# InterfacesA_USBFTDI.net
KiCad netlist of a schematic drawn in Altium Designer
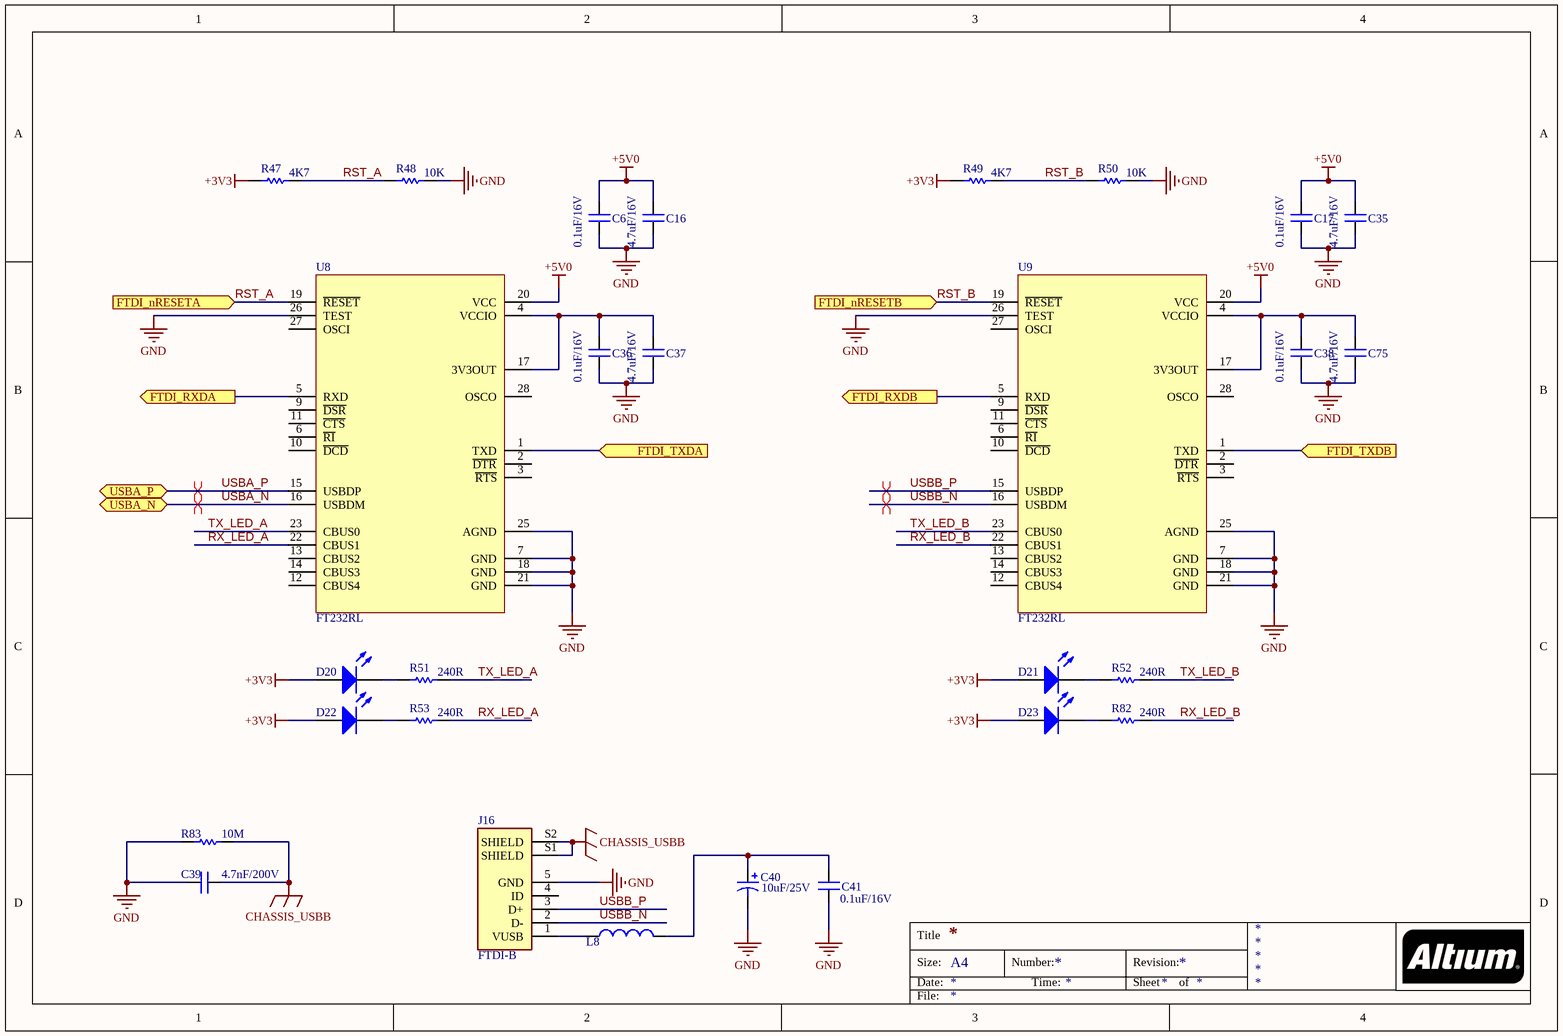
[diagram p0: InterfacesA_USBFTDI.SchDoc]

(export (version "E")
  (design (tool "Eeschema 10.0.6"))
  (components
    (comp (ref "C6")
      (value "0.1uF/16V")
      (footprint "CAP_0805")
      (fields (field (name "Comment") "CAP_0805"))
      (libsource (lib "LibSGQB") (part "CAP_0603"))
    )
    (comp (ref "C16")
      (value "4.7uF/16V")
      (footprint "CAP_0805")
      (fields (field (name "Comment") "CAP_0805"))
      (libsource (lib "LibSGQB") (part "CAP_0603"))
    )
    (comp (ref "C17")
      (value "0.1uF/16V")
      (footprint "CAP_0805")
      (fields (field (name "Comment") "CAP_0805"))
      (libsource (lib "LibSGQB") (part "CAP_0603"))
    )
    (comp (ref "C35")
      (value "4.7uF/16V")
      (footprint "CAP_0805")
      (fields (field (name "Comment") "CAP_0805"))
      (libsource (lib "LibSGQB") (part "CAP_0603"))
    )
    (comp (ref "C36")
      (value "0.1uF/16V")
      (footprint "CAP_0805")
      (fields (field (name "Comment") "CAP_0805"))
      (libsource (lib "LibSGQB") (part "CAP_0603"))
    )
    (comp (ref "C37")
      (value "4.7uF/16V")
      (footprint "CAP_0805")
      (fields (field (name "Comment") "CAP_0805"))
      (libsource (lib "LibSGQB") (part "CAP_0603"))
    )
    (comp (ref "C38")
      (value "0.1uF/16V")
      (footprint "CAP_0805")
      (fields (field (name "Comment") "CAP_0805"))
      (libsource (lib "LibSGQB") (part "CAP_0603"))
    )
    (comp (ref "C39")
      (value "4.7nF/200V")
      (footprint "CAP_0805")
      (fields (field (name "Comment") "CAP_0805"))
      (libsource (lib "AdapterLib") (part "CAP_0805"))
    )
    (comp (ref "C40")
      (value "10uF/25V")
      (footprint "CASE-C")
      (fields (field (name "Comment") "CASE-C"))
      (libsource (lib "AdapterLib") (part "CASE-C"))
    )
    (comp (ref "C41")
      (value "0.1uF/16V")
      (footprint "CAP_0805")
      (fields (field (name "Comment") "CAP_0805"))
      (libsource (lib "AdapterLib") (part "CAP_0805"))
    )
    (comp (ref "C75")
      (value "4.7uF/16V")
      (footprint "CAP_0805")
      (fields (field (name "Comment") "CAP_0805"))
      (libsource (lib "LibSGQB") (part "CAP_0603"))
    )
    (comp (ref "D20")
      (value "LED_0603")
      (footprint "LED_0603")
      (libsource (lib "AdapterLib") (part "LED_0603"))
    )
    (comp (ref "D21")
      (value "LED_0603")
      (footprint "LED_0603")
      (libsource (lib "AdapterLib") (part "LED_0603"))
    )
    (comp (ref "D22")
      (value "LED_0603")
      (footprint "LED_0603")
      (libsource (lib "AdapterLib") (part "LED_0603"))
    )
    (comp (ref "D23")
      (value "LED_0603")
      (footprint "LED_0603")
      (libsource (lib "AdapterLib") (part "LED_0603"))
    )
    (comp (ref "J16")
      (value "FTDI-B")
      (footprint "UX60-MB-5S8")
      (description "USB MINI TYPE B")
      (libsource (lib "AdapterLib") (part "UX60-MB-5S8"))
    )
    (comp (ref "L8")
      (value "IND_0805")
      (footprint "IND_0805")
      (libsource (lib "AdapterLib") (part "IND_0805"))
    )
    (comp (ref "R47")
      (value "4K7")
      (footprint "RES_0805")
      (fields (field (name "Comment") "RES_0805"))
      (libsource (lib "AdapterLib") (part "RES_0805"))
    )
    (comp (ref "R48")
      (value "10K")
      (footprint "RES_0805")
      (fields (field (name "Comment") "RES_0805"))
      (libsource (lib "AdapterLib") (part "RES_0805"))
    )
    (comp (ref "R49")
      (value "4K7")
      (footprint "RES_0805")
      (fields (field (name "Comment") "RES_0805"))
      (libsource (lib "AdapterLib") (part "RES_0805"))
    )
    (comp (ref "R50")
      (value "10K")
      (footprint "RES_0805")
      (fields (field (name "Comment") "RES_0805"))
      (libsource (lib "AdapterLib") (part "RES_0805"))
    )
    (comp (ref "R51")
      (value "240R")
      (footprint "RES_0805")
      (fields (field (name "Comment") "RES_0805"))
      (libsource (lib "AdapterLib") (part "RES_0805"))
    )
    (comp (ref "R52")
      (value "240R")
      (footprint "RES_0805")
      (fields (field (name "Comment") "RES_0805"))
      (libsource (lib "AdapterLib") (part "RES_0805"))
    )
    (comp (ref "R53")
      (value "240R")
      (footprint "RES_0805")
      (fields (field (name "Comment") "RES_0805"))
      (libsource (lib "AdapterLib") (part "RES_0805"))
    )
    (comp (ref "R82")
      (value "240R")
      (footprint "RES_0805")
      (fields (field (name "Comment") "RES_0805"))
      (libsource (lib "AdapterLib") (part "RES_0805"))
    )
    (comp (ref "R83")
      (value "10M")
      (footprint "RES_0805")
      (fields (field (name "Comment") "RES_0805"))
      (libsource (lib "AdapterLib") (part "RES_0805"))
    )
    (comp (ref "U8")
      (value "FT232RL")
      (footprint "AdapterLib:FT232RL")
      (description "USB Bridge, USB to UART USB 2.0 UART Interface 28-SSOP")
      (fields (field (name "DIGI-KEY_PART_NUMBER") "768-1007-1-ND") (field (name "MP") "FT232RL-REEL"))
      (libsource (lib "AdapterLib") (part "FT232RL"))
    )
    (comp (ref "U9")
      (value "FT232RL")
      (footprint "AdapterLib:FT232RL")
      (description "USB Bridge, USB to UART USB 2.0 UART Interface 28-SSOP")
      (fields (field (name "DIGI-KEY_PART_NUMBER") "768-1007-1-ND") (field (name "MP") "FT232RL-REEL"))
      (libsource (lib "AdapterLib") (part "FT232RL"))
    )
  )
  (nets
    (net (code "1") (name "+3V3") (class "Default")
      (node (ref "D20") (pin "1") (pinfunction "A_1") (pintype "passive"))
      (node (ref "D21") (pin "1") (pinfunction "A_1") (pintype "passive"))
      (node (ref "D22") (pin "1") (pinfunction "A_1") (pintype "passive"))
      (node (ref "D23") (pin "1") (pinfunction "A_1") (pintype "passive"))
      (node (ref "R47") (pin "1") (pinfunction "1_1") (pintype "passive"))
      (node (ref "R49") (pin "1") (pinfunction "1_1") (pintype "passive"))
    )
    (net (code "2") (name "+5V0") (class "Default")
      (node (ref "C16") (pin "1") (pinfunction "1_1") (pintype "passive"))
      (node (ref "C17") (pin "1") (pinfunction "1_1") (pintype "passive"))
      (node (ref "C35") (pin "1") (pinfunction "1_1") (pintype "passive"))
      (node (ref "C6") (pin "1") (pinfunction "1_1") (pintype "passive"))
      (node (ref "U8") (pin "20") (pinfunction "VCC_20") (pintype "passive"))
      (node (ref "U9") (pin "20") (pinfunction "VCC_20") (pintype "passive"))
    )
    (net (code "3") (name "/FTDI_RXDA") (class "Default")
      (node (ref "U8") (pin "5") (pinfunction "RXD_5") (pintype "passive"))
    )
    (net (code "4") (name "/FTDI_RXDB") (class "Default")
      (node (ref "U9") (pin "5") (pinfunction "RXD_5") (pintype "passive"))
    )
    (net (code "5") (name "/FTDI_TXDA") (class "Default")
      (node (ref "U8") (pin "1") (pinfunction "TXD_1") (pintype "passive"))
    )
    (net (code "6") (name "/FTDI_TXDB") (class "Default")
      (node (ref "U9") (pin "1") (pinfunction "TXD_1") (pintype "passive"))
    )
    (net (code "7") (name "/RST_A") (class "Default")
      (node (ref "R47") (pin "2") (pinfunction "2_2") (pintype "passive"))
      (node (ref "R48") (pin "1") (pinfunction "1_1") (pintype "passive"))
      (node (ref "U8") (pin "19") (pinfunction "~{RESET}_19") (pintype "passive"))
    )
    (net (code "8") (name "/RST_B") (class "Default")
      (node (ref "R49") (pin "2") (pinfunction "2_2") (pintype "passive"))
      (node (ref "R50") (pin "1") (pinfunction "1_1") (pintype "passive"))
      (node (ref "U9") (pin "19") (pinfunction "~{RESET}_19") (pintype "passive"))
    )
    (net (code "9") (name "/RX_LED_A") (class "Default")
      (node (ref "R53") (pin "2") (pinfunction "2_2") (pintype "passive"))
      (node (ref "U8") (pin "22") (pinfunction "CBUS1_22") (pintype "passive"))
    )
    (net (code "10") (name "/RX_LED_B") (class "Default")
      (node (ref "R82") (pin "2") (pinfunction "2_2") (pintype "passive"))
      (node (ref "U9") (pin "22") (pinfunction "CBUS1_22") (pintype "passive"))
    )
    (net (code "11") (name "/TX_LED_A") (class "Default")
      (node (ref "R51") (pin "2") (pinfunction "2_2") (pintype "passive"))
      (node (ref "U8") (pin "23") (pinfunction "CBUS0_23") (pintype "passive"))
    )
    (net (code "12") (name "/TX_LED_B") (class "Default")
      (node (ref "R52") (pin "2") (pinfunction "2_2") (pintype "passive"))
      (node (ref "U9") (pin "23") (pinfunction "CBUS0_23") (pintype "passive"))
    )
    (net (code "13") (name "/USBA_N") (class "Default")
      (node (ref "U8") (pin "16") (pinfunction "USBDM_16") (pintype "passive"))
    )
    (net (code "14") (name "/USBA_P") (class "Default")
      (node (ref "U8") (pin "15") (pinfunction "USBDP_15") (pintype "passive"))
    )
    (net (code "15") (name "/USBB_N") (class "Default")
      (node (ref "J16") (pin "2") (pinfunction "D-_2") (pintype "passive"))
      (node (ref "U9") (pin "16") (pinfunction "USBDM_16") (pintype "passive"))
    )
    (net (code "16") (name "/USBB_P") (class "Default")
      (node (ref "J16") (pin "3") (pinfunction "D+_3") (pintype "passive"))
      (node (ref "U9") (pin "15") (pinfunction "USBDP_15") (pintype "passive"))
    )
    (net (code "17") (name "CHASSIS_USBB") (class "Default")
      (node (ref "C39") (pin "1") (pinfunction "1_1") (pintype "passive"))
      (node (ref "J16") (pin "S1") (pinfunction "SHIELD_S1") (pintype "passive"))
      (node (ref "J16") (pin "S2") (pinfunction "SHIELD_S2") (pintype "passive"))
      (node (ref "R83") (pin "1") (pinfunction "1_1") (pintype "passive"))
    )
    (net (code "18") (name "GND") (class "Default")
      (node (ref "C16") (pin "2") (pinfunction "2_2") (pintype "passive"))
      (node (ref "C17") (pin "2") (pinfunction "2_2") (pintype "passive"))
      (node (ref "C35") (pin "2") (pinfunction "2_2") (pintype "passive"))
      (node (ref "C36") (pin "2") (pinfunction "2_2") (pintype "passive"))
      (node (ref "C37") (pin "2") (pinfunction "2_2") (pintype "passive"))
      (node (ref "C38") (pin "2") (pinfunction "2_2") (pintype "passive"))
      (node (ref "C39") (pin "2") (pinfunction "2_2") (pintype "passive"))
      (node (ref "C40") (pin "K") (pinfunction "2_K") (pintype "passive"))
      (node (ref "C41") (pin "1") (pinfunction "1_1") (pintype "passive"))
      (node (ref "C6") (pin "2") (pinfunction "2_2") (pintype "passive"))
      (node (ref "C75") (pin "2") (pinfunction "2_2") (pintype "passive"))
      (node (ref "J16") (pin "5") (pinfunction "GND_5") (pintype "passive"))
      (node (ref "R48") (pin "2") (pinfunction "2_2") (pintype "passive"))
      (node (ref "R50") (pin "2") (pinfunction "2_2") (pintype "passive"))
      (node (ref "R83") (pin "2") (pinfunction "2_2") (pintype "passive"))
      (node (ref "U8") (pin "18") (pinfunction "GND_18") (pintype "passive"))
      (node (ref "U8") (pin "21") (pinfunction "GND_21") (pintype "passive"))
      (node (ref "U8") (pin "25") (pinfunction "AGND_25") (pintype "passive"))
      (node (ref "U8") (pin "26") (pinfunction "TEST_26") (pintype "passive"))
      (node (ref "U8") (pin "7") (pinfunction "GND_7") (pintype "passive"))
      (node (ref "U9") (pin "18") (pinfunction "GND_18") (pintype "passive"))
      (node (ref "U9") (pin "21") (pinfunction "GND_21") (pintype "passive"))
      (node (ref "U9") (pin "25") (pinfunction "AGND_25") (pintype "passive"))
      (node (ref "U9") (pin "26") (pinfunction "TEST_26") (pintype "passive"))
      (node (ref "U9") (pin "7") (pinfunction "GND_7") (pintype "passive"))
    )
    (net (code "19") (name "Net-(C40-1)") (class "Default")
      (node (ref "C40") (pin "A") (pinfunction "1_A") (pintype "passive"))
      (node (ref "C41") (pin "2") (pinfunction "2_2") (pintype "passive"))
      (node (ref "L8") (pin "2") (pinfunction "2_2") (pintype "passive"))
    )
    (net (code "20") (name "Net-(D20-K)") (class "Default")
      (node (ref "D20") (pin "2") (pinfunction "K_2") (pintype "passive"))
      (node (ref "R51") (pin "1") (pinfunction "1_1") (pintype "passive"))
    )
    (net (code "21") (name "Net-(D21-K)") (class "Default")
      (node (ref "D21") (pin "2") (pinfunction "K_2") (pintype "passive"))
      (node (ref "R52") (pin "1") (pinfunction "1_1") (pintype "passive"))
    )
    (net (code "22") (name "Net-(D22-K)") (class "Default")
      (node (ref "D22") (pin "2") (pinfunction "K_2") (pintype "passive"))
      (node (ref "R53") (pin "1") (pinfunction "1_1") (pintype "passive"))
    )
    (net (code "23") (name "Net-(D23-K)") (class "Default")
      (node (ref "D23") (pin "2") (pinfunction "K_2") (pintype "passive"))
      (node (ref "R82") (pin "1") (pinfunction "1_1") (pintype "passive"))
    )
    (net (code "24") (name "Net-(J16-VUSB)") (class "Default")
      (node (ref "J16") (pin "1") (pinfunction "VUSB_1") (pintype "passive"))
      (node (ref "L8") (pin "1") (pinfunction "1_1") (pintype "passive"))
    )
    (net (code "25") (name "Net-(U8-3V3OUT)") (class "Default")
      (node (ref "C36") (pin "1") (pinfunction "1_1") (pintype "passive"))
      (node (ref "C37") (pin "1") (pinfunction "1_1") (pintype "passive"))
      (node (ref "U8") (pin "17") (pinfunction "3V3OUT_17") (pintype "passive"))
      (node (ref "U8") (pin "4") (pinfunction "VCCIO_4") (pintype "passive"))
    )
    (net (code "26") (name "Net-(U9-3V3OUT)") (class "Default")
      (node (ref "C38") (pin "1") (pinfunction "1_1") (pintype "passive"))
      (node (ref "C75") (pin "1") (pinfunction "1_1") (pintype "passive"))
      (node (ref "U9") (pin "17") (pinfunction "3V3OUT_17") (pintype "passive"))
      (node (ref "U9") (pin "4") (pinfunction "VCCIO_4") (pintype "passive"))
    )
    (net (code "27") (name "unconnected-(J16-ID-Pad4)") (class "Default")
      (node (ref "J16") (pin "4") (pinfunction "ID_4") (pintype "passive"))
    )
    (net (code "28") (name "unconnected-(U8-CBUS2-Pad13)") (class "Default")
      (node (ref "U8") (pin "13") (pinfunction "CBUS2_13") (pintype "passive"))
    )
    (net (code "29") (name "unconnected-(U8-CBUS3-Pad14)") (class "Default")
      (node (ref "U8") (pin "14") (pinfunction "CBUS3_14") (pintype "passive"))
    )
    (net (code "30") (name "unconnected-(U8-CBUS4-Pad12)") (class "Default")
      (node (ref "U8") (pin "12") (pinfunction "CBUS4_12") (pintype "passive"))
    )
    (net (code "31") (name "unconnected-(U8-OSCI-Pad27)") (class "Default")
      (node (ref "U8") (pin "27") (pinfunction "OSCI_27") (pintype "passive"))
    )
    (net (code "32") (name "unconnected-(U8-OSCO-Pad28)") (class "Default")
      (node (ref "U8") (pin "28") (pinfunction "OSCO_28") (pintype "passive"))
    )
    (net (code "33") (name "unconnected-(U8-~{CTS}-Pad11)") (class "Default")
      (node (ref "U8") (pin "11") (pinfunction "~{CTS}_11") (pintype "passive"))
    )
    (net (code "34") (name "unconnected-(U8-~{DCD}-Pad10)") (class "Default")
      (node (ref "U8") (pin "10") (pinfunction "~{DCD}_10") (pintype "passive"))
    )
    (net (code "35") (name "unconnected-(U8-~{DSR}-Pad9)") (class "Default")
      (node (ref "U8") (pin "9") (pinfunction "~{DSR}_9") (pintype "passive"))
    )
    (net (code "36") (name "unconnected-(U8-~{DTR}-Pad2)") (class "Default")
      (node (ref "U8") (pin "2") (pinfunction "~{DTR}_2") (pintype "passive"))
    )
    (net (code "37") (name "unconnected-(U8-~{RI}-Pad6)") (class "Default")
      (node (ref "U8") (pin "6") (pinfunction "~{RI}_6") (pintype "passive"))
    )
    (net (code "38") (name "unconnected-(U8-~{RTS}-Pad3)") (class "Default")
      (node (ref "U8") (pin "3") (pinfunction "~{RTS}_3") (pintype "passive"))
    )
    (net (code "39") (name "unconnected-(U9-CBUS2-Pad13)") (class "Default")
      (node (ref "U9") (pin "13") (pinfunction "CBUS2_13") (pintype "passive"))
    )
    (net (code "40") (name "unconnected-(U9-CBUS3-Pad14)") (class "Default")
      (node (ref "U9") (pin "14") (pinfunction "CBUS3_14") (pintype "passive"))
    )
    (net (code "41") (name "unconnected-(U9-CBUS4-Pad12)") (class "Default")
      (node (ref "U9") (pin "12") (pinfunction "CBUS4_12") (pintype "passive"))
    )
    (net (code "42") (name "unconnected-(U9-OSCI-Pad27)") (class "Default")
      (node (ref "U9") (pin "27") (pinfunction "OSCI_27") (pintype "passive"))
    )
    (net (code "43") (name "unconnected-(U9-OSCO-Pad28)") (class "Default")
      (node (ref "U9") (pin "28") (pinfunction "OSCO_28") (pintype "passive"))
    )
    (net (code "44") (name "unconnected-(U9-~{CTS}-Pad11)") (class "Default")
      (node (ref "U9") (pin "11") (pinfunction "~{CTS}_11") (pintype "passive"))
    )
    (net (code "45") (name "unconnected-(U9-~{DCD}-Pad10)") (class "Default")
      (node (ref "U9") (pin "10") (pinfunction "~{DCD}_10") (pintype "passive"))
    )
    (net (code "46") (name "unconnected-(U9-~{DSR}-Pad9)") (class "Default")
      (node (ref "U9") (pin "9") (pinfunction "~{DSR}_9") (pintype "passive"))
    )
    (net (code "47") (name "unconnected-(U9-~{DTR}-Pad2)") (class "Default")
      (node (ref "U9") (pin "2") (pinfunction "~{DTR}_2") (pintype "passive"))
    )
    (net (code "48") (name "unconnected-(U9-~{RI}-Pad6)") (class "Default")
      (node (ref "U9") (pin "6") (pinfunction "~{RI}_6") (pintype "passive"))
    )
    (net (code "49") (name "unconnected-(U9-~{RTS}-Pad3)") (class "Default")
      (node (ref "U9") (pin "3") (pinfunction "~{RTS}_3") (pintype "passive"))
    )
  )
)
